# LDOConverterSchematic.net
KiCad netlist of a schematic drawn in Altium Designer
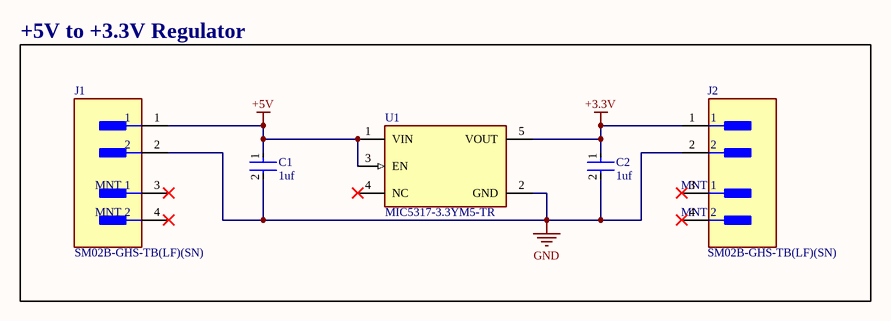
[diagram p0: LDOConverterSchematic.SchDoc]

(export (version "E")
  (design (tool "Eeschema 10.0.6"))
  (components
    (comp (ref "C1")
      (value "1uf")
      (footprint "FP-CC0805-0_85-MFG")
      (description "CAP CER 1UF 10V X5R 0805")
      (fields
        (field (name "TOLERANCE") "0.1")
        (field (name "OCTOPART") "https://octopart.com/cc0805kkx5r6bb105-yageo-9292777")
      )
      (libsource (lib "Altium Content Vault") (part "11868f565c42a9108669ba33697ecf6"))
    )
    (comp (ref "C2")
      (value "1uf")
      (footprint "FP-CC0805-0_85-MFG")
      (description "CAP CER 1UF 10V X5R 0805")
      (fields
        (field (name "TOLERANCE") "0.1")
        (field (name "OCTOPART") "https://octopart.com/cc0805kkx5r6bb105-yageo-9292777")
      )
      (libsource (lib "Altium Content Vault") (part "11868f565c42a9108669ba33697ecf6"))
    )
    (comp (ref "J1")
      (value "SM02B-GHS-TB(LF)(SN)")
      (footprint "FP-SM02B-GHS-TB_LF_SN-MFG")
      (description "CONN HEADER SMD R/A 2POS 1.25MM")
      (libsource (lib "") (part "56ec3178a87b3978bdc1b3682cd516a_1"))
    )
    (comp (ref "J2")
      (value "SM02B-GHS-TB(LF)(SN)")
      (footprint "FP-SM02B-GHS-TB_LF_SN-MFG")
      (description "CONN HEADER SMD R/A 2POS 1.25MM")
      (libsource (lib "Altium Content Vault") (part "56ec3178a87b3978bdc1b3682cd516a"))
    )
    (comp (ref "U1")
      (value "MIC5317-3.3YM5-TR")
      (footprint "FP-SOT23-5LD-PL-1-MFG")
      (description "IC REG LINEAR 3.3V 150MA SOT23-5")
      (libsource (lib "Altium Content Vault") (part "0a093dae7315cdc977fd108dde87457"))
    )
  )
  (nets
    (net (code "1") (name "+3.3V") (class "Default")
      (node (ref "C2") (pin "1") (pinfunction "1_1") (pintype "passive"))
      (node (ref "J2") (pin "1") (pinfunction "1_1") (pintype "passive"))
      (node (ref "U1") (pin "5") (pinfunction "VOUT_5") (pintype "power_in"))
    )
    (net (code "2") (name "+5V") (class "Default")
      (node (ref "C1") (pin "1") (pinfunction "1_1") (pintype "passive"))
      (node (ref "J1") (pin "1") (pinfunction "1_1") (pintype "passive"))
      (node (ref "U1") (pin "1") (pinfunction "VIN_1") (pintype "power_in"))
      (node (ref "U1") (pin "3") (pinfunction "EN_3") (pintype "input"))
    )
    (net (code "3") (name "GND") (class "Default")
      (node (ref "C1") (pin "2") (pinfunction "2_2") (pintype "passive"))
      (node (ref "C2") (pin "2") (pinfunction "2_2") (pintype "passive"))
      (node (ref "J1") (pin "2") (pinfunction "2_2") (pintype "passive"))
      (node (ref "J2") (pin "2") (pinfunction "2_2") (pintype "passive"))
      (node (ref "U1") (pin "2") (pinfunction "GND_2") (pintype "power_in"))
    )
    (net (code "4") (name "unconnected-(J1-MNT_1-Pad3)") (class "Default")
      (node (ref "J1") (pin "3") (pinfunction "MNT_1_3") (pintype "passive+no_connect"))
    )
    (net (code "5") (name "unconnected-(J1-MNT_2-Pad4)") (class "Default")
      (node (ref "J1") (pin "4") (pinfunction "MNT_2_4") (pintype "passive+no_connect"))
    )
    (net (code "6") (name "unconnected-(J2-MNT_1-Pad3)") (class "Default")
      (node (ref "J2") (pin "3") (pinfunction "MNT_1_3") (pintype "passive+no_connect"))
    )
    (net (code "7") (name "unconnected-(J2-MNT_2-Pad4)") (class "Default")
      (node (ref "J2") (pin "4") (pinfunction "MNT_2_4") (pintype "passive+no_connect"))
    )
    (net (code "8") (name "unconnected-(U1-NC-Pad4)") (class "Default")
      (node (ref "U1") (pin "4") (pinfunction "NC_4") (pintype "passive+no_connect"))
    )
  )
)
